# USB.net
KiCad netlist of a schematic drawn in Altium Designer
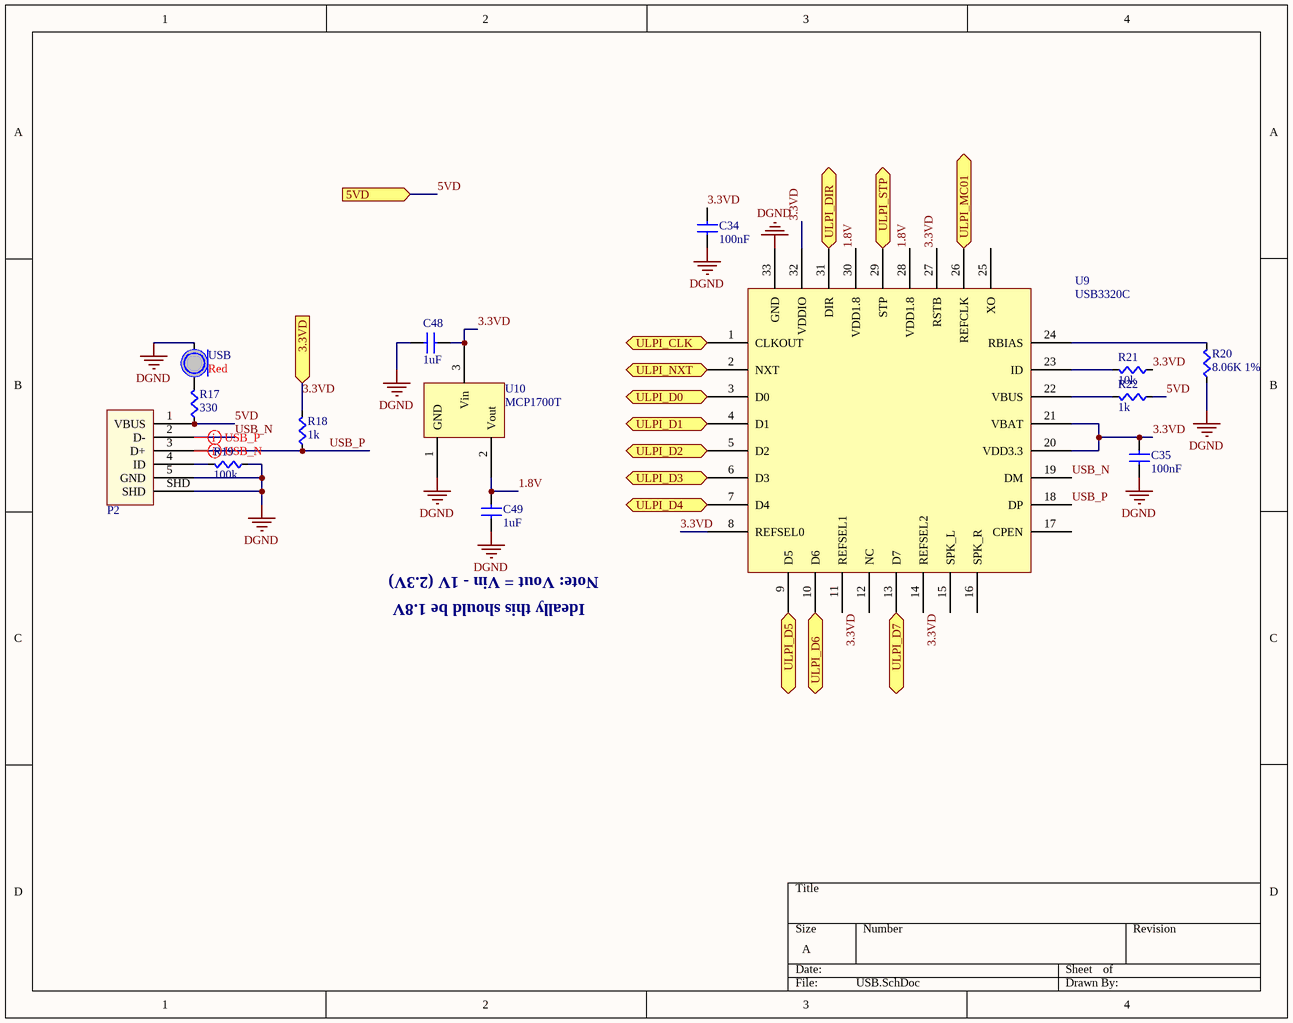
[diagram p0: USB.SchDoc]

(export (version "E")
  (design (tool "Eeschema 10.0.6"))
  (components
    (comp (ref "C34")
      (value "100nF")
      (footprint "CAPC0603")
      (fields (field (name "Comment") "Cap"))
      (libsource (lib "SubjuGator8") (part "Cap"))
    )
    (comp (ref "C35")
      (value "100nF")
      (footprint "CAPC0603")
      (fields (field (name "Comment") "Cap"))
      (libsource (lib "SubjuGator8") (part "Cap"))
    )
    (comp (ref "C48")
      (value "1uF")
      (footprint "CAPC0603")
      (fields (field (name "Comment") "Cap"))
      (libsource (lib "SubjuGator8") (part "Cap"))
    )
    (comp (ref "C49")
      (value "1uF")
      (footprint "CAPC0603")
      (fields (field (name "Comment") "Cap"))
      (libsource (lib "SubjuGator8") (part "Cap"))
    )
    (comp (ref "P2")
      (value "USB Micro")
      (footprint "10118192-0001LF")
      (description "USB Mini B Metal Shield SMT")
      (libsource (lib "SubjuGator8") (part "USB Micro"))
    )
    (comp (ref "R17")
      (value "330")
      (footprint "RES0603")
      (fields (field (name "Comment") "Res"))
      (libsource (lib "Passives") (part "Res"))
    )
    (comp (ref "R18")
      (value "1k")
      (footprint "RES0603")
      (fields (field (name "Comment") "Res"))
      (libsource (lib "Passives") (part "Res"))
    )
    (comp (ref "R19")
      (value "100k")
      (footprint "RES0603")
      (fields (field (name "Comment") "Res"))
      (libsource (lib "Passives") (part "Res"))
    )
    (comp (ref "R20")
      (value "8.06K 1%")
      (footprint "RES0603")
      (fields (field (name "Comment") "Res"))
      (libsource (lib "Passives") (part "Res"))
    )
    (comp (ref "R21")
      (value "10k")
      (footprint "RES0603")
      (fields (field (name "Comment") "Res"))
      (libsource (lib "Passives") (part "Res"))
    )
    (comp (ref "R22")
      (value "1k")
      (footprint "RES0603")
      (fields (field (name "Comment") "Res"))
      (libsource (lib "Passives") (part "Res"))
    )
    (comp (ref "U9")
      (value "USB3320C")
      (footprint "QFN-32")
      (description "MULTI-FREQ USB 2.0 ULPI PHY")
      (libsource (lib "ICs") (part "USB3320C"))
    )
    (comp (ref "U10")
      (value "MCP1700T")
      (footprint "SOT23-3")
      (description "IC REG LDO 1.8V 0.2A SOT23-3")
      (libsource (lib "SubjuGator8") (part "LDO 1.8V"))
    )
    (comp (ref "USB")
      (value "LED")
      (footprint "LED0805")
      (fields (field (name "COLOR") "Red"))
      (libsource (lib "Semiconductors") (part "LED"))
    )
  )
  (nets
    (net (code "1") (name "/1.8V") (class "Default")
      (node (ref "C49") (pin "1") (pinfunction "A_1") (pintype "passive"))
      (node (ref "U10") (pin "2") (pinfunction "Vout_2") (pintype "passive"))
      (node (ref "U9") (pin "28") (pinfunction "VDD1.8_28") (pintype "passive"))
      (node (ref "U9") (pin "30") (pinfunction "VDD1.8_30") (pintype "passive"))
    )
    (net (code "2") (name "/3.3VD") (class "Default")
      (node (ref "C34") (pin "1") (pinfunction "A_1") (pintype "passive"))
      (node (ref "C35") (pin "1") (pinfunction "A_1") (pintype "passive"))
      (node (ref "C48") (pin "1") (pinfunction "A_1") (pintype "passive"))
      (node (ref "R18") (pin "1") (pinfunction "A_1") (pintype "passive"))
      (node (ref "R21") (pin "2") (pinfunction "B_2") (pintype "passive"))
      (node (ref "U10") (pin "3") (pinfunction "Vin_3") (pintype "passive"))
      (node (ref "U9") (pin "11") (pinfunction "REFSEL1_11") (pintype "passive"))
      (node (ref "U9") (pin "14") (pinfunction "REFSEL2_14") (pintype "passive"))
      (node (ref "U9") (pin "20") (pinfunction "VDD3.3_20") (pintype "passive"))
      (node (ref "U9") (pin "21") (pinfunction "VBAT_21") (pintype "passive"))
      (node (ref "U9") (pin "27") (pinfunction "RSTB_27") (pintype "passive"))
      (node (ref "U9") (pin "32") (pinfunction "VDDIO_32") (pintype "passive"))
      (node (ref "U9") (pin "8") (pinfunction "REFSEL0_8") (pintype "passive"))
    )
    (net (code "3") (name "/5VD") (class "Default")
      (node (ref "P2") (pin "1") (pinfunction "VBUS_1") (pintype "passive"))
      (node (ref "R17") (pin "2") (pinfunction "B_2") (pintype "passive"))
      (node (ref "R22") (pin "2") (pinfunction "B_2") (pintype "passive"))
    )
    (net (code "4") (name "/ULPI_CLK") (class "Default")
      (node (ref "U9") (pin "1") (pinfunction "CLKOUT_1") (pintype "passive"))
    )
    (net (code "5") (name "/ULPI_D0") (class "Default")
      (node (ref "U9") (pin "3") (pinfunction "D0_3") (pintype "passive"))
    )
    (net (code "6") (name "/ULPI_D1") (class "Default")
      (node (ref "U9") (pin "4") (pinfunction "D1_4") (pintype "passive"))
    )
    (net (code "7") (name "/ULPI_D2") (class "Default")
      (node (ref "U9") (pin "5") (pinfunction "D2_5") (pintype "passive"))
    )
    (net (code "8") (name "/ULPI_D3") (class "Default")
      (node (ref "U9") (pin "6") (pinfunction "D3_6") (pintype "passive"))
    )
    (net (code "9") (name "/ULPI_D4") (class "Default")
      (node (ref "U9") (pin "7") (pinfunction "D4_7") (pintype "passive"))
    )
    (net (code "10") (name "/ULPI_D5") (class "Default")
      (node (ref "U9") (pin "9") (pinfunction "D5_9") (pintype "passive"))
    )
    (net (code "11") (name "/ULPI_D6") (class "Default")
      (node (ref "U9") (pin "10") (pinfunction "D6_10") (pintype "passive"))
    )
    (net (code "12") (name "/ULPI_D7") (class "Default")
      (node (ref "U9") (pin "13") (pinfunction "D7_13") (pintype "passive"))
    )
    (net (code "13") (name "/ULPI_DIR") (class "Default")
      (node (ref "U9") (pin "31") (pinfunction "DIR_31") (pintype "passive"))
    )
    (net (code "14") (name "/ULPI_MC01") (class "Default")
      (node (ref "U9") (pin "26") (pinfunction "REFCLK_26") (pintype "passive"))
    )
    (net (code "15") (name "/ULPI_NXT") (class "Default")
      (node (ref "U9") (pin "2") (pinfunction "NXT_2") (pintype "passive"))
    )
    (net (code "16") (name "/ULPI_STP") (class "Default")
      (node (ref "U9") (pin "29") (pinfunction "STP_29") (pintype "passive"))
    )
    (net (code "17") (name "/USB_N") (class "Default")
      (node (ref "P2") (pin "2") (pinfunction "D-_2") (pintype "passive"))
      (node (ref "U9") (pin "19") (pinfunction "DM_19") (pintype "passive"))
    )
    (net (code "18") (name "/USB_P") (class "Default")
      (node (ref "P2") (pin "3") (pinfunction "D+_3") (pintype "passive"))
      (node (ref "R18") (pin "2") (pinfunction "B_2") (pintype "passive"))
      (node (ref "U9") (pin "18") (pinfunction "DP_18") (pintype "passive"))
    )
    (net (code "19") (name "DGND") (class "Default")
      (node (ref "C34") (pin "2") (pinfunction "B_2") (pintype "passive"))
      (node (ref "C35") (pin "2") (pinfunction "B_2") (pintype "passive"))
      (node (ref "C48") (pin "2") (pinfunction "B_2") (pintype "passive"))
      (node (ref "C49") (pin "2") (pinfunction "B_2") (pintype "passive"))
      (node (ref "P2") (pin "5") (pinfunction "GND_5") (pintype "passive"))
      (node (ref "P2") (pin "SHD") (pinfunction "SHD_SHD") (pintype "passive"))
      (node (ref "R19") (pin "2") (pinfunction "B_2") (pintype "passive"))
      (node (ref "R20") (pin "2") (pinfunction "B_2") (pintype "passive"))
      (node (ref "U10") (pin "1") (pinfunction "GND_1") (pintype "passive"))
      (node (ref "U9") (pin "33") (pinfunction "GND_33") (pintype "passive"))
      (node (ref "USB") (pin "C") (pinfunction "C_C") (pintype "passive"))
    )
    (net (code "20") (name "Net-(P2-ID)") (class "Default")
      (node (ref "P2") (pin "4") (pinfunction "ID_4") (pintype "passive"))
      (node (ref "R19") (pin "1") (pinfunction "A_1") (pintype "passive"))
    )
    (net (code "21") (name "Net-(R17-A)") (class "Default")
      (node (ref "R17") (pin "1") (pinfunction "A_1") (pintype "passive"))
      (node (ref "USB") (pin "A") (pinfunction "A_A") (pintype "passive"))
    )
    (net (code "22") (name "Net-(R20-A)") (class "Default")
      (node (ref "R20") (pin "1") (pinfunction "A_1") (pintype "passive"))
      (node (ref "U9") (pin "24") (pinfunction "RBIAS_24") (pintype "passive"))
    )
    (net (code "23") (name "Net-(R21-A)") (class "Default")
      (node (ref "R21") (pin "1") (pinfunction "A_1") (pintype "passive"))
      (node (ref "U9") (pin "23") (pinfunction "ID_23") (pintype "passive"))
    )
    (net (code "24") (name "Net-(R22-A)") (class "Default")
      (node (ref "R22") (pin "1") (pinfunction "A_1") (pintype "passive"))
      (node (ref "U9") (pin "22") (pinfunction "VBUS_22") (pintype "passive"))
    )
    (net (code "25") (name "unconnected-(U9-CPEN-Pad17)") (class "Default")
      (node (ref "U9") (pin "17") (pinfunction "CPEN_17") (pintype "passive"))
    )
    (net (code "26") (name "unconnected-(U9-NC-Pad12)") (class "Default")
      (node (ref "U9") (pin "12") (pinfunction "NC_12") (pintype "passive"))
    )
    (net (code "27") (name "unconnected-(U9-SPK_L-Pad15)") (class "Default")
      (node (ref "U9") (pin "15") (pinfunction "SPK_L_15") (pintype "passive"))
    )
    (net (code "28") (name "unconnected-(U9-SPK_R-Pad16)") (class "Default")
      (node (ref "U9") (pin "16") (pinfunction "SPK_R_16") (pintype "passive"))
    )
    (net (code "29") (name "unconnected-(U9-XO-Pad25)") (class "Default")
      (node (ref "U9") (pin "25") (pinfunction "XO_25") (pintype "passive"))
    )
  )
)
